# SCH.net
KiCad netlist of a schematic drawn in Altium Designer
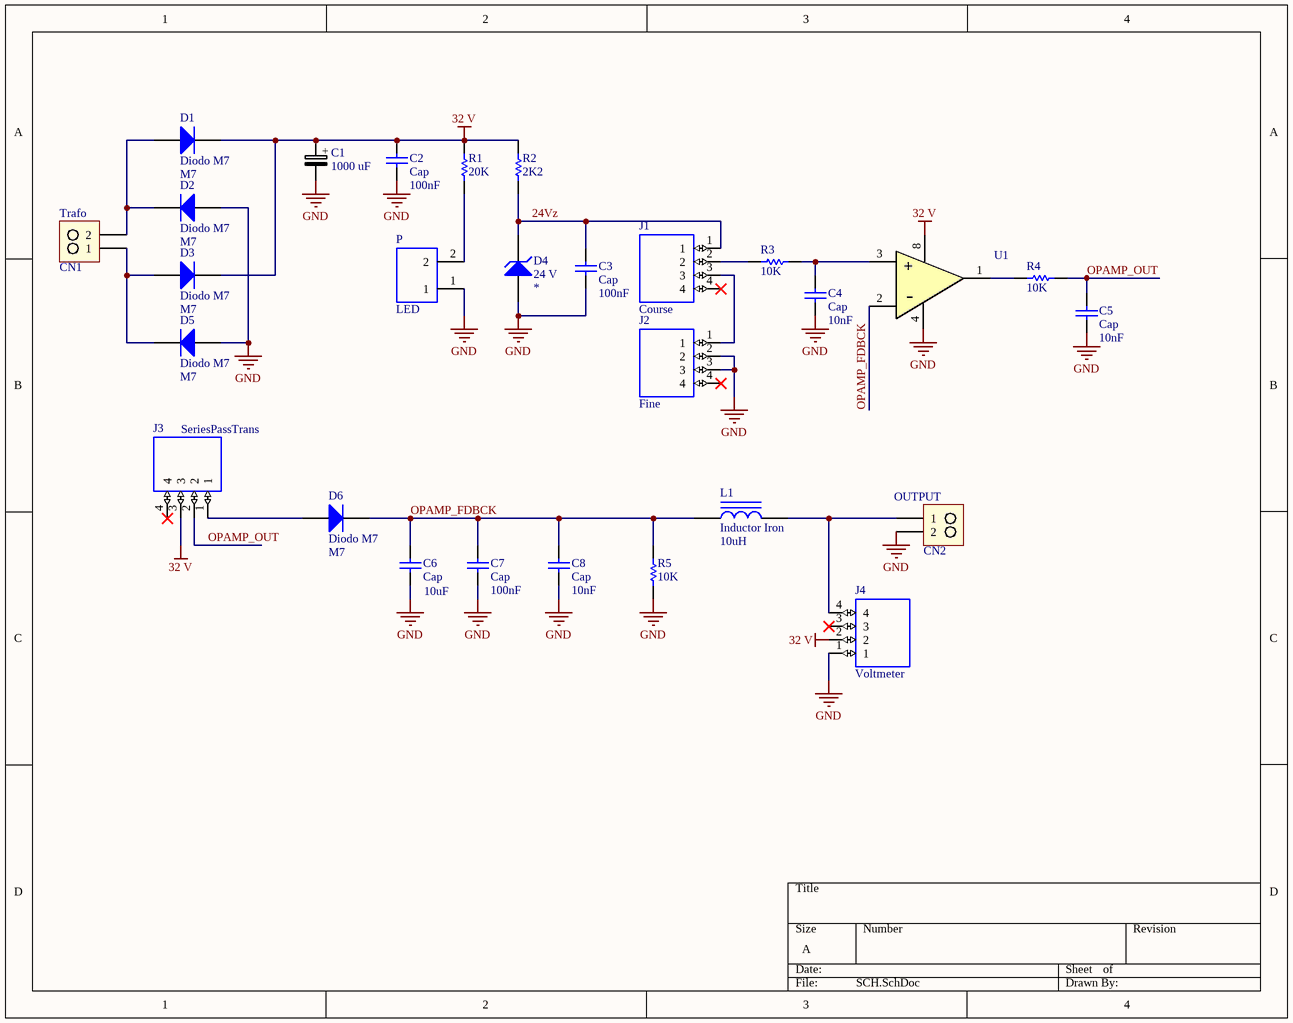
[diagram p0: SCH.SchDoc]

(export (version "E")
  (design (tool "Eeschema 10.0.6"))
  (components
    (comp (ref "C1")
      (value "1000 uF")
      (footprint "CAP-POL-D12.5-P5.0")
      (description "Capacitor eletrolítico")
      (fields (field (name "Comment") "Cap Pol"))
      (libsource (lib "Passivos") (part "Cap Pol"))
    )
    (comp (ref "C2")
      (value "Cap")
      (footprint "SMD0805")
      (description "Capacitor")
      (fields (field (name "ALTIUM_VALUE") "100nF") (field (name "PUBLISHER") "Altium Limited"))
      (libsource (lib "Passivos") (part "Cap"))
    )
    (comp (ref "C3")
      (value "Cap")
      (footprint "SMD0805")
      (description "Capacitor")
      (fields (field (name "ALTIUM_VALUE") "100nF") (field (name "PUBLISHER") "Altium Limited"))
      (libsource (lib "Passivos") (part "Cap"))
    )
    (comp (ref "C4")
      (value "Cap")
      (footprint "SMD1210")
      (description "Capacitor")
      (fields (field (name "ALTIUM_VALUE") "10nF") (field (name "PUBLISHER") "Altium Limited"))
      (libsource (lib "Passivos") (part "Cap"))
    )
    (comp (ref "C5")
      (value "Cap")
      (footprint "SMD1210")
      (description "Capacitor")
      (fields (field (name "ALTIUM_VALUE") "10nF") (field (name "PUBLISHER") "Altium Limited"))
      (libsource (lib "Passivos") (part "Cap"))
    )
    (comp (ref "C6")
      (value "Cap")
      (footprint "SMD0805")
      (description "Capacitor")
      (fields (field (name "ALTIUM_VALUE") "10uF") (field (name "PUBLISHER") "Altium Limited"))
      (libsource (lib "Passivos") (part "Cap"))
    )
    (comp (ref "C7")
      (value "Cap")
      (footprint "SMD0805")
      (description "Capacitor")
      (fields (field (name "ALTIUM_VALUE") "100nF") (field (name "PUBLISHER") "Altium Limited"))
      (libsource (lib "Passivos") (part "Cap"))
    )
    (comp (ref "C8")
      (value "Cap")
      (footprint "SMD1210")
      (description "Capacitor")
      (fields (field (name "ALTIUM_VALUE") "10nF") (field (name "PUBLISHER") "Altium Limited"))
      (libsource (lib "Passivos") (part "Cap"))
    )
    (comp (ref "CN1")
      (value "Trafo")
      (footprint "BORNE 2Vias")
      (description "Borne 2 vias")
      (fields (field (name "PARTNUM") "AKZ700-2"))
      (libsource (lib "") (part "BORNE-2_1"))
    )
    (comp (ref "CN2")
      (value "OUTPUT")
      (footprint "BORNE 2Vias")
      (description "Borne 2 vias")
      (fields (field (name "PARTNUM") "AKZ700-2"))
      (libsource (lib "Conector") (part "BORNE-2"))
    )
    (comp (ref "D1")
      (value "Diodo M7")
      (footprint "DIODE_DO-214AC")
      (description "1 Amp General Purpose Rectifier")
      (fields (field (name "ALTIUM_VALUE") "M7") (field (name "PUBLISHER") "Altium Limited"))
      (libsource (lib "Diodos") (part "Diodo M7"))
    )
    (comp (ref "D2")
      (value "Diodo M7")
      (footprint "DIODE_DO-214AC")
      (description "1 Amp General Purpose Rectifier")
      (fields (field (name "ALTIUM_VALUE") "M7") (field (name "PUBLISHER") "Altium Limited"))
      (libsource (lib "Diodos") (part "Diodo M7"))
    )
    (comp (ref "D3")
      (value "Diodo M7")
      (footprint "DIODE_DO-214AC")
      (description "1 Amp General Purpose Rectifier")
      (fields (field (name "ALTIUM_VALUE") "M7") (field (name "PUBLISHER") "Altium Limited"))
      (libsource (lib "Diodos") (part "Diodo M7"))
    )
    (comp (ref "D4")
      (value "24 V")
      (footprint "Resistor 1/4W")
      (description "Zener Diode")
      (fields (field (name "ALTIUM_VALUE") "*") (field (name "PUBLISHER") "Altium Limited"))
      (libsource (lib "Diodos") (part "Diodo zener TVS"))
    )
    (comp (ref "D5")
      (value "Diodo M7")
      (footprint "DIODE_DO-214AC")
      (description "1 Amp General Purpose Rectifier")
      (fields (field (name "ALTIUM_VALUE") "M7") (field (name "PUBLISHER") "Altium Limited"))
      (libsource (lib "Diodos") (part "Diodo M7"))
    )
    (comp (ref "D6")
      (value "Diodo M7")
      (footprint "DIODE_DO-214AC")
      (description "1 Amp General Purpose Rectifier")
      (fields (field (name "ALTIUM_VALUE") "M7") (field (name "PUBLISHER") "Altium Limited"))
      (libsource (lib "Diodos") (part "Diodo M7"))
    )
    (comp (ref "J1")
      (value "Course")
      (footprint "470533000")
      (description "KKÂ® 254 Vertical Header, with Friction Lock, 4 Circuits, PC Tail Length: 4.00mm")
      (fields (field (name "MF") "Molex") (field (name "MP") "47053-3000"))
      (libsource (lib "Schlib1") (part "47053-3000"))
    )
    (comp (ref "J2")
      (value "Fine")
      (footprint "470533000")
      (description "KKÂ® 254 Vertical Header, with Friction Lock, 4 Circuits, PC Tail Length: 4.00mm")
      (fields (field (name "MF") "Molex") (field (name "MP") "47053-3000"))
      (libsource (lib "Schlib1") (part "47053-3000"))
    )
    (comp (ref "J3")
      (value "SeriesPassTrans")
      (footprint "470533000")
      (description "KKÂ® 254 Vertical Header, with Friction Lock, 4 Circuits, PC Tail Length: 4.00mm")
      (fields (field (name "MF") "Molex") (field (name "MP") "47053-3000"))
      (libsource (lib "Schlib1") (part "47053-3000"))
    )
    (comp (ref "J4")
      (value "Voltmeter")
      (footprint "470533000")
      (description "KKÂ® 254 Vertical Header, with Friction Lock, 4 Circuits, PC Tail Length: 4.00mm")
      (fields (field (name "MF") "Molex") (field (name "MP") "47053-3000"))
      (libsource (lib "Schlib1") (part "47053-3000"))
    )
    (comp (ref "L1")
      (value "Inductor Iron")
      (footprint "WURTH_6823")
      (description "Magnetic-Core Inductor")
      (fields (field (name "ALTIUM_VALUE") "10uH") (field (name "PUBLISHER") "Altium Limited"))
      (libsource (lib "Passivos") (part "Inductor Iron"))
    )
    (comp (ref "P")
      (value "LED")
      (footprint "MOLEX_0022272021")
      (description "Connector Header Through Hole 2 position 0.100 _2.54mm_")
      (fields (field (name "MP") "0022272021") (field (name "MF") "Molex"))
      (libsource (lib "Schlib1") (part "0022272021"))
    )
    (comp (ref "R1")
      (value "20K")
      (footprint "Resistor0805")
      (description "Resistor")
      (fields (field (name "Comment") "Res1") (field (name "PUBLISHER") "Altium Limited"))
      (libsource (lib "Passivos") (part "Res1"))
    )
    (comp (ref "R2")
      (value "2K2")
      (footprint "Resistor0805")
      (description "Resistor")
      (fields (field (name "Comment") "Res1") (field (name "PUBLISHER") "Altium Limited"))
      (libsource (lib "Passivos") (part "Res1"))
    )
    (comp (ref "R3")
      (value "10K")
      (footprint "Resistor0805")
      (description "Resistor")
      (fields (field (name "Comment") "Res1") (field (name "PUBLISHER") "Altium Limited"))
      (libsource (lib "Passivos") (part "Res1"))
    )
    (comp (ref "R4")
      (value "10K")
      (footprint "Resistor0805")
      (description "Resistor")
      (fields (field (name "Comment") "Res1") (field (name "PUBLISHER") "Altium Limited"))
      (libsource (lib "Passivos") (part "Res1"))
    )
    (comp (ref "R5")
      (value "10K")
      (footprint "Resistor0805")
      (description "Resistor")
      (fields (field (name "Comment") "Res1") (field (name "PUBLISHER") "Altium Limited"))
      (libsource (lib "Passivos") (part "Res1"))
    )
    (comp (ref "U1") (value "LM358") (footprint "DIP8") (libsource (lib "Schlib1") (part "LM358")))
  )
  (nets
    (net (code "1") (name "/24Vz") (class "Default")
      (node (ref "C3") (pin "2") (pinfunction "2_2") (pintype "passive"))
      (node (ref "D4") (pin "2") (pinfunction "K_2") (pintype "passive"))
      (node (ref "J1") (pin "1") (pinfunction "1_1") (pintype "bidirectional"))
      (node (ref "R2") (pin "1") (pinfunction "1_1") (pintype "passive"))
    )
    (net (code "2") (name "/OPAMP_FDBCK") (class "Default")
      (node (ref "C6") (pin "2") (pinfunction "2_2") (pintype "passive"))
      (node (ref "C7") (pin "2") (pinfunction "2_2") (pintype "passive"))
      (node (ref "C8") (pin "2") (pinfunction "2_2") (pintype "passive"))
      (node (ref "D6") (pin "2") (pinfunction "K_2") (pintype "passive"))
      (node (ref "L1") (pin "1") (pinfunction "1_1") (pintype "passive"))
      (node (ref "R5") (pin "2") (pinfunction "2_2") (pintype "passive"))
      (node (ref "U1") (pin "2") (pinfunction "2_2") (pintype "passive"))
    )
    (net (code "3") (name "/OPAMP_OUT") (class "Default")
      (node (ref "C5") (pin "2") (pinfunction "2_2") (pintype "passive"))
      (node (ref "J3") (pin "2") (pinfunction "2_2") (pintype "bidirectional"))
      (node (ref "R4") (pin "1") (pinfunction "1_1") (pintype "passive"))
    )
    (net (code "4") (name "32 V") (class "Default")
      (node (ref "C1") (pin "1") (pinfunction "1_1") (pintype "passive"))
      (node (ref "C2") (pin "2") (pinfunction "2_2") (pintype "passive"))
      (node (ref "D1") (pin "2") (pinfunction "K_2") (pintype "passive"))
      (node (ref "D3") (pin "2") (pinfunction "K_2") (pintype "passive"))
      (node (ref "J3") (pin "3") (pinfunction "3_3") (pintype "bidirectional"))
      (node (ref "J4") (pin "2") (pinfunction "2_2") (pintype "bidirectional"))
      (node (ref "R1") (pin "2") (pinfunction "2_2") (pintype "passive"))
      (node (ref "R2") (pin "2") (pinfunction "2_2") (pintype "passive"))
      (node (ref "U1") (pin "8") (pinfunction "83_8") (pintype "passive"))
    )
    (net (code "5") (name "GND") (class "Default")
      (node (ref "C1") (pin "2") (pinfunction "2_2") (pintype "passive"))
      (node (ref "C2") (pin "1") (pinfunction "1_1") (pintype "passive"))
      (node (ref "C3") (pin "1") (pinfunction "1_1") (pintype "passive"))
      (node (ref "C4") (pin "1") (pinfunction "1_1") (pintype "passive"))
      (node (ref "C5") (pin "1") (pinfunction "1_1") (pintype "passive"))
      (node (ref "C6") (pin "1") (pinfunction "1_1") (pintype "passive"))
      (node (ref "C7") (pin "1") (pinfunction "1_1") (pintype "passive"))
      (node (ref "C8") (pin "1") (pinfunction "1_1") (pintype "passive"))
      (node (ref "CN2") (pin "2") (pinfunction "2_2") (pintype "passive"))
      (node (ref "D2") (pin "1") (pinfunction "A_1") (pintype "passive"))
      (node (ref "D4") (pin "1") (pinfunction "A_1") (pintype "passive"))
      (node (ref "D5") (pin "1") (pinfunction "A_1") (pintype "passive"))
      (node (ref "J2") (pin "2") (pinfunction "2_2") (pintype "bidirectional"))
      (node (ref "J2") (pin "3") (pinfunction "3_3") (pintype "bidirectional"))
      (node (ref "J4") (pin "1") (pinfunction "1_1") (pintype "bidirectional"))
      (node (ref "P") (pin "1") (pinfunction "1_1") (pintype "passive"))
      (node (ref "R5") (pin "1") (pinfunction "1_1") (pintype "passive"))
      (node (ref "U1") (pin "4") (pinfunction "4_4") (pintype "passive"))
    )
    (net (code "6") (name "Net-(C4-Pad2)") (class "Default")
      (node (ref "C4") (pin "2") (pinfunction "2_2") (pintype "passive"))
      (node (ref "R3") (pin "1") (pinfunction "1_1") (pintype "passive"))
      (node (ref "U1") (pin "3") (pinfunction "3_3") (pintype "passive"))
    )
    (net (code "7") (name "Net-(CN2-Pad1)") (class "Default")
      (node (ref "CN2") (pin "1") (pinfunction "1_1") (pintype "passive"))
      (node (ref "J4") (pin "4") (pinfunction "4_4") (pintype "bidirectional"))
      (node (ref "L1") (pin "2") (pinfunction "2_2") (pintype "passive"))
    )
    (net (code "8") (name "Net-(D1-A)") (class "Default")
      (node (ref "CN1") (pin "2") (pinfunction "2_2") (pintype "passive"))
      (node (ref "D1") (pin "1") (pinfunction "A_1") (pintype "passive"))
      (node (ref "D2") (pin "2") (pinfunction "K_2") (pintype "passive"))
    )
    (net (code "9") (name "Net-(D3-A)") (class "Default")
      (node (ref "CN1") (pin "1") (pinfunction "1_1") (pintype "passive"))
      (node (ref "D3") (pin "1") (pinfunction "A_1") (pintype "passive"))
      (node (ref "D5") (pin "2") (pinfunction "K_2") (pintype "passive"))
    )
    (net (code "10") (name "Net-(D6-A)") (class "Default")
      (node (ref "D6") (pin "1") (pinfunction "A_1") (pintype "passive"))
      (node (ref "J3") (pin "1") (pinfunction "1_1") (pintype "bidirectional"))
    )
    (net (code "11") (name "Net-(J1-Pad2)") (class "Default")
      (node (ref "J1") (pin "2") (pinfunction "2_2") (pintype "bidirectional"))
      (node (ref "R3") (pin "2") (pinfunction "2_2") (pintype "passive"))
    )
    (net (code "12") (name "Net-(J1-Pad3)") (class "Default")
      (node (ref "J1") (pin "3") (pinfunction "3_3") (pintype "bidirectional"))
      (node (ref "J2") (pin "1") (pinfunction "1_1") (pintype "bidirectional"))
    )
    (net (code "13") (name "Net-(P-Pad2)") (class "Default")
      (node (ref "P") (pin "2") (pinfunction "2_2") (pintype "passive"))
      (node (ref "R1") (pin "1") (pinfunction "1_1") (pintype "passive"))
    )
    (net (code "14") (name "Net-(R4-Pad2)") (class "Default")
      (node (ref "R4") (pin "2") (pinfunction "2_2") (pintype "passive"))
      (node (ref "U1") (pin "1") (pinfunction "1_1") (pintype "passive"))
    )
    (net (code "15") (name "unconnected-(J1-Pad4)") (class "Default")
      (node (ref "J1") (pin "4") (pinfunction "4_4") (pintype "bidirectional+no_connect"))
    )
    (net (code "16") (name "unconnected-(J2-Pad4)") (class "Default")
      (node (ref "J2") (pin "4") (pinfunction "4_4") (pintype "bidirectional+no_connect"))
    )
    (net (code "17") (name "unconnected-(J3-Pad4)") (class "Default")
      (node (ref "J3") (pin "4") (pinfunction "4_4") (pintype "bidirectional+no_connect"))
    )
    (net (code "18") (name "unconnected-(J4-Pad3)") (class "Default")
      (node (ref "J4") (pin "3") (pinfunction "3_3") (pintype "bidirectional+no_connect"))
    )
  )
)
